# LPEDT_revA1_bikeit_DISPLAY_MECH.net
KiCad netlist of a schematic drawn in Altium Designer
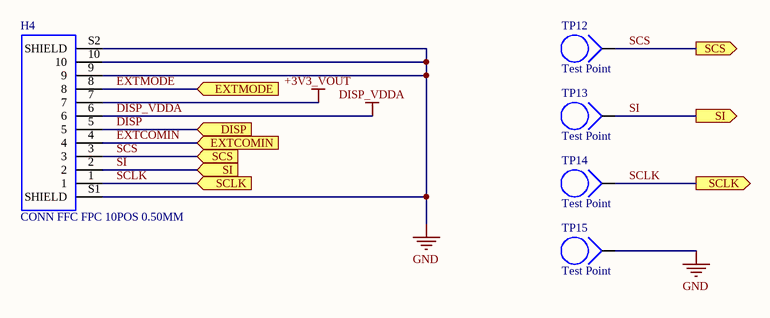
[diagram p0: LPEDT_revA1_bikeit_DISPLAY_MECH.SchDoc]

(export (version "E")
  (design (tool "Eeschema 10.0.6"))
  (components
    (comp (ref "H4")
      (value "CONN FFC FPC 10POS 0.50MM")
      (footprint "AYF531035A")
      (description "10 Position 0.5 mm Solder Right Angle FFC / FPC SMD Socket")
      (fields
        (field (name "MANUFACTURER") "Panasonic")
        (field (name "MANUFACTURER PART NUMBER") "AYF531035A")
      )
      (libsource (lib "LPEDT_revA1_bikeit_IL") (part "AYF531035A"))
    )
    (comp (ref "TP12") (value "Test Point") (libsource (lib "LPEDT_revA1_bikeit_IL") (part "Test Pad")))
    (comp (ref "TP13") (value "Test Point") (libsource (lib "LPEDT_revA1_bikeit_IL") (part "Test Pad")))
    (comp (ref "TP14") (value "Test Point") (libsource (lib "LPEDT_revA1_bikeit_IL") (part "Test Pad")))
    (comp (ref "TP15") (value "Test Point") (libsource (lib "LPEDT_revA1_bikeit_IL") (part "Test Pad")))
  )
  (nets
    (net (code "1") (name "+3V3_VOUT") (class "Default")
      (node (ref "H4") (pin "7") (pinfunction "7_7") (pintype "passive"))
    )
    (net (code "2") (name "/DISP") (class "Default")
      (node (ref "H4") (pin "5") (pinfunction "5_5") (pintype "passive"))
    )
    (net (code "3") (name "/EXTCOMIN") (class "Default")
      (node (ref "H4") (pin "4") (pinfunction "4_4") (pintype "passive"))
    )
    (net (code "4") (name "/EXTMODE") (class "Default")
      (node (ref "H4") (pin "8") (pinfunction "8_8") (pintype "passive"))
    )
    (net (code "5") (name "/SCLK") (class "Default")
      (node (ref "H4") (pin "1") (pinfunction "1_1") (pintype "passive"))
      (node (ref "TP14") (pin "1") (pinfunction "1_1") (pintype "passive"))
    )
    (net (code "6") (name "/SCS") (class "Default")
      (node (ref "H4") (pin "3") (pinfunction "3_3") (pintype "passive"))
      (node (ref "TP12") (pin "1") (pinfunction "1_1") (pintype "passive"))
    )
    (net (code "7") (name "/SI") (class "Default")
      (node (ref "H4") (pin "2") (pinfunction "2_2") (pintype "passive"))
      (node (ref "TP13") (pin "1") (pinfunction "1_1") (pintype "passive"))
    )
    (net (code "8") (name "DISP_VDDA") (class "Default")
      (node (ref "H4") (pin "6") (pinfunction "6_6") (pintype "passive"))
    )
    (net (code "9") (name "GND") (class "Default")
      (node (ref "H4") (pin "10") (pinfunction "10_10") (pintype "passive"))
      (node (ref "H4") (pin "9") (pinfunction "9_9") (pintype "passive"))
      (node (ref "H4") (pin "S1") (pinfunction "SHIELD_S1") (pintype "passive"))
      (node (ref "H4") (pin "S2") (pinfunction "SHIELD_S2") (pintype "passive"))
      (node (ref "TP15") (pin "1") (pinfunction "1_1") (pintype "passive"))
    )
  )
)
